# Cool_Stuff_USB_Hub.net
KiCad netlist of a schematic drawn in EasyEDA Pro
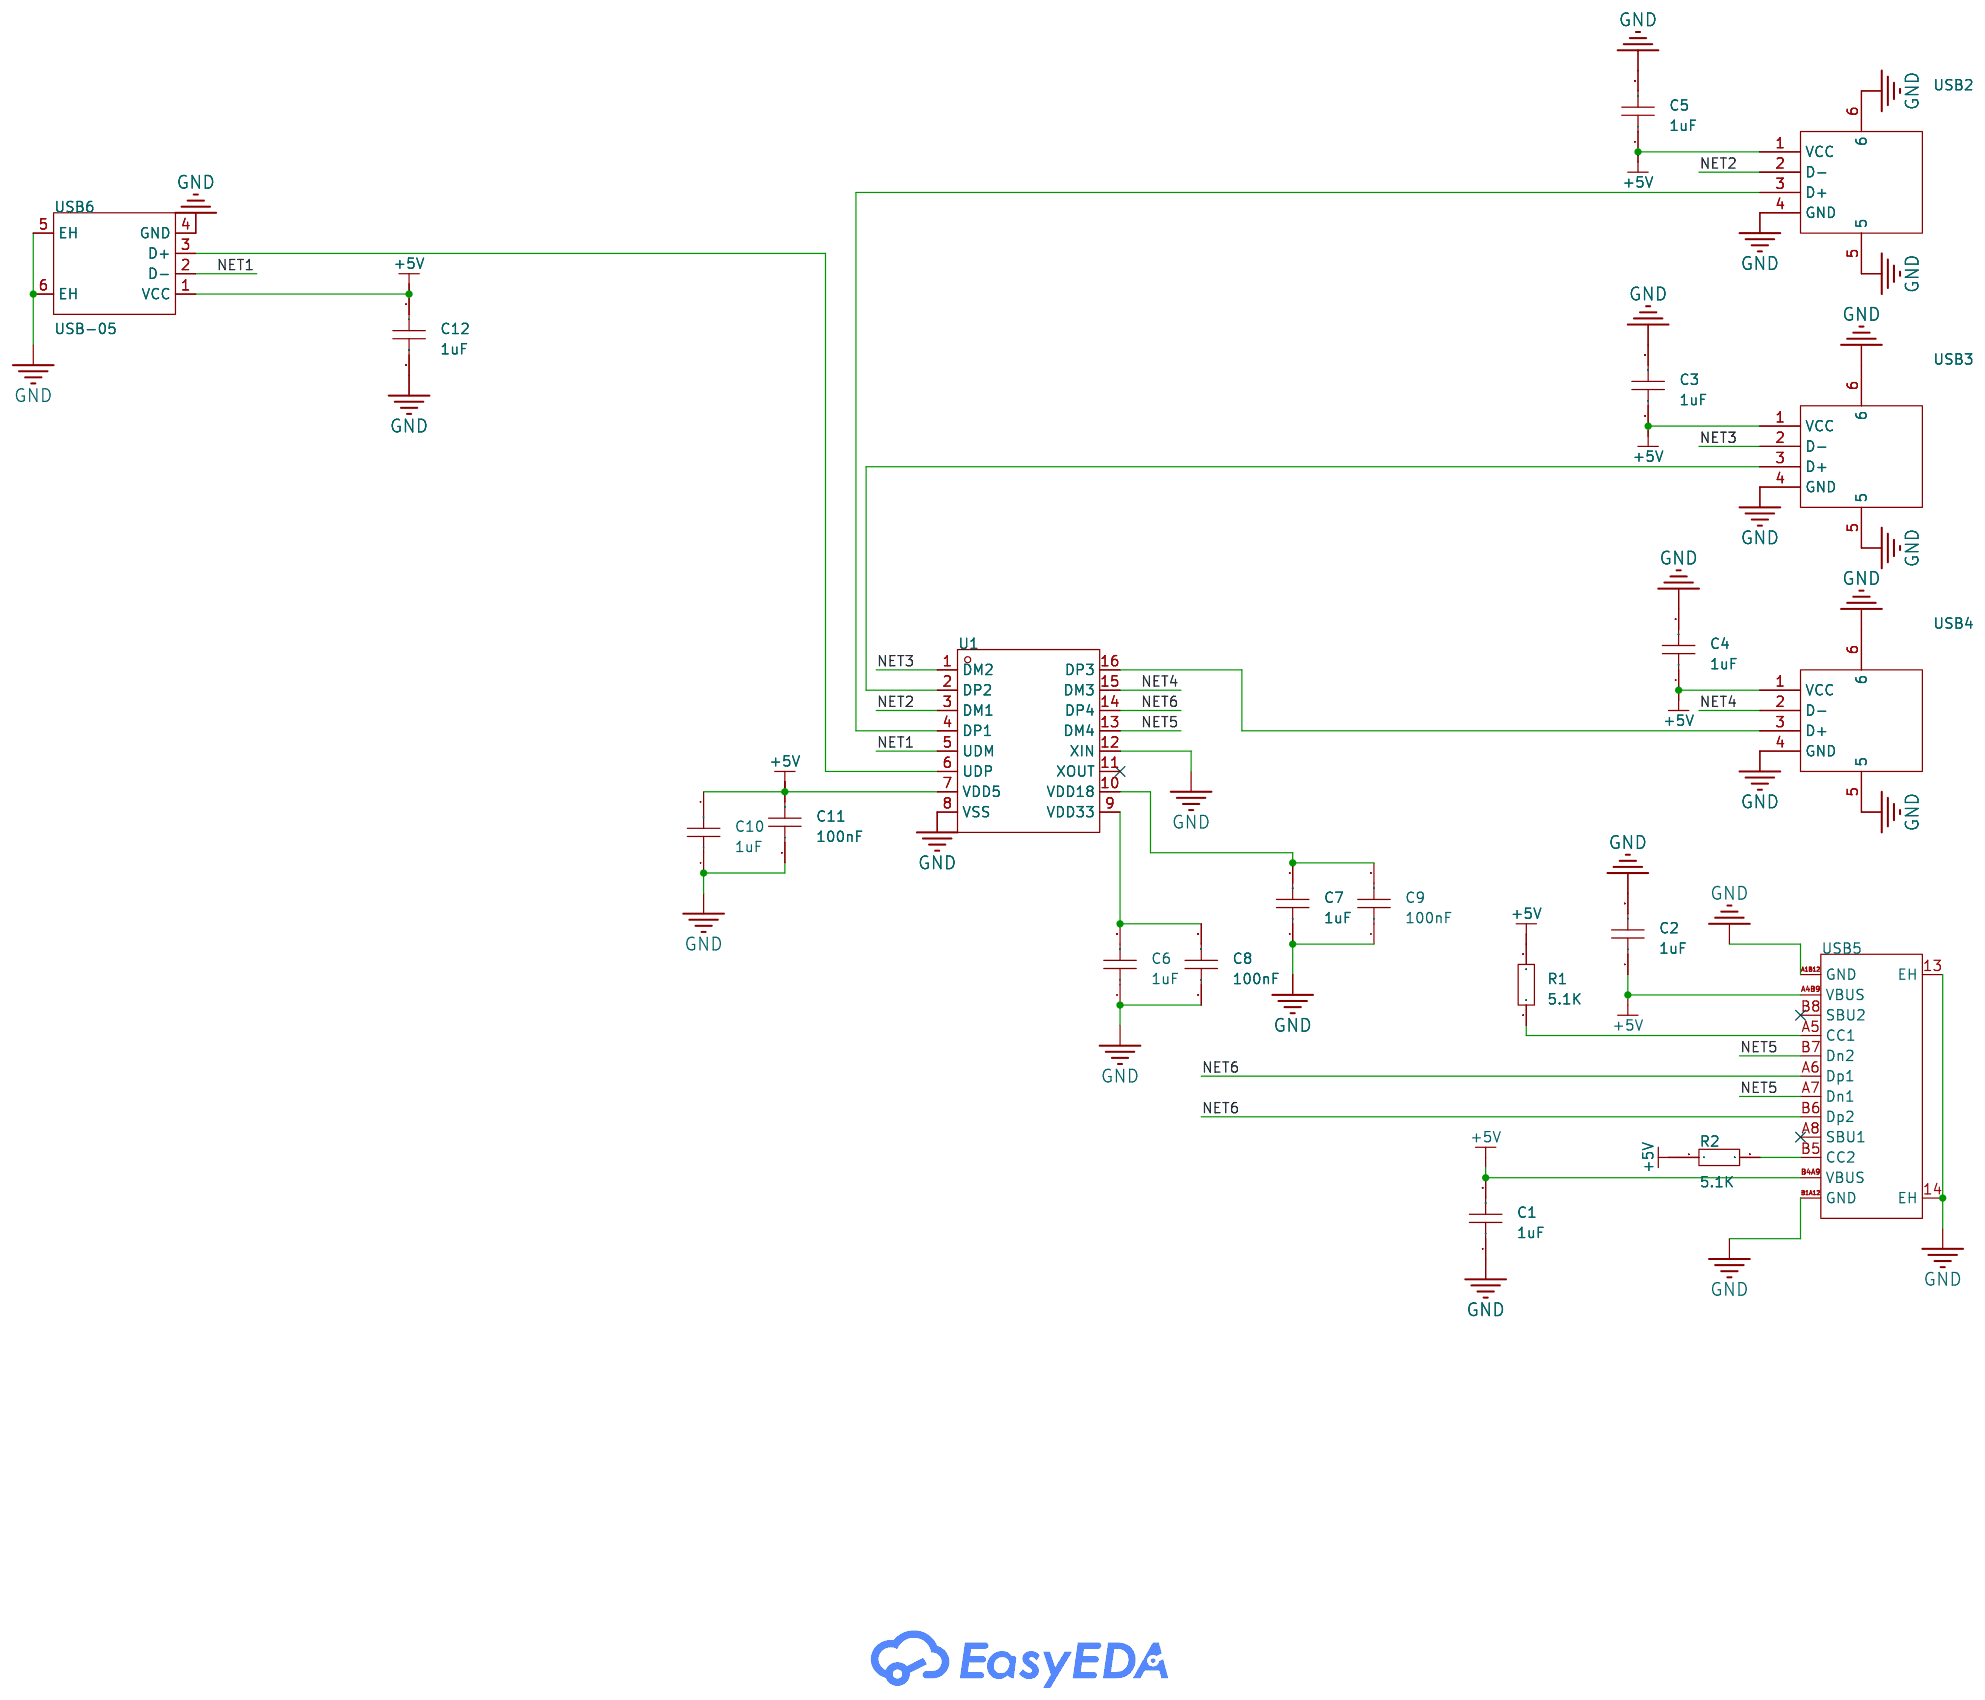
[diagram p0: schematic sheet]

(export (version "E")
  (design (tool "Eeschema 10.0.6"))
  (components
    (comp (ref "C1") (value "1uF") (footprint "easyedapro:C0603") (libsource (lib "easyedapro") (part "CAP")))
    (comp (ref "C2") (value "1uF") (footprint "easyedapro:C0603") (libsource (lib "easyedapro") (part "CAP")))
    (comp (ref "C3") (value "1uF") (footprint "easyedapro:C0603") (libsource (lib "easyedapro") (part "CAP")))
    (comp (ref "C4") (value "1uF") (footprint "easyedapro:C0603") (libsource (lib "easyedapro") (part "CAP")))
    (comp (ref "C5") (value "1uF") (footprint "easyedapro:C0603") (libsource (lib "easyedapro") (part "CAP")))
    (comp (ref "C6") (value "1uF") (footprint "easyedapro:C0603") (libsource (lib "easyedapro") (part "CAP")))
    (comp (ref "C7") (value "1uF") (footprint "easyedapro:C0603") (libsource (lib "easyedapro") (part "CAP")))
    (comp (ref "C8")
      (value "100nF")
      (footprint "easyedapro:C0603")
      (libsource (lib "easyedapro") (part "CAP"))
    )
    (comp (ref "C9")
      (value "100nF")
      (footprint "easyedapro:C0603")
      (libsource (lib "easyedapro") (part "CAP"))
    )
    (comp (ref "C10")
      (value "1uF")
      (footprint "easyedapro:C0603")
      (libsource (lib "easyedapro") (part "CAP"))
    )
    (comp (ref "C11")
      (value "100nF")
      (footprint "easyedapro:C0603")
      (libsource (lib "easyedapro") (part "CAP"))
    )
    (comp (ref "C12")
      (value "1uF")
      (footprint "easyedapro:C0603")
      (libsource (lib "easyedapro") (part "CAP"))
    )
    (comp (ref "R1")
      (value "5.1K")
      (footprint "easyedapro:R0603")
      (libsource (lib "easyedapro") (part "Res"))
    )
    (comp (ref "R2")
      (value "5.1K")
      (footprint "easyedapro:R0603")
      (libsource (lib "easyedapro") (part "Res"))
    )
    (comp (ref "U1")
      (value "SL2.1s")
      (footprint "easyedapro:SSOP-16_L4.6-W2.6-P0.53-LS4.0-BL")
      (fields (field (name "Manufacturer") "CoreChips(和芯润德)"))
      (libsource (lib "easyedapro") (part "SL2.1S"))
    )
    (comp (ref "USB2")
      (value "10.0 QHHTZB6.3")
      (footprint "easyedapro:USB-A-TH_10.0QHHTZB6.3")
      (fields (field (name "Manufacturer") "SHOU HAN(首韩)"))
      (libsource (lib "easyedapro") (part "10.0 QHHTZB6.3"))
    )
    (comp (ref "USB3")
      (value "10.0 QHHTZB6.3")
      (footprint "easyedapro:USB-A-TH_10.0QHHTZB6.3")
      (fields (field (name "Manufacturer") "SHOU HAN(首韩)"))
      (libsource (lib "easyedapro") (part "10.0 QHHTZB6.3"))
    )
    (comp (ref "USB4")
      (value "10.0 QHHTZB6.3")
      (footprint "easyedapro:USB-A-TH_10.0QHHTZB6.3")
      (fields (field (name "Manufacturer") "SHOU HAN(首韩)"))
      (libsource (lib "easyedapro") (part "10.0 QHHTZB6.3"))
    )
    (comp (ref "USB5")
      (value "TYPE-C 16PIN 2MD(073)")
      (footprint "easyedapro:USB-C-SMD_TYPE-C-16PIN-2MD-073")
      (fields (field (name "Manufacturer") "SHOU HAN(首韩)"))
      (libsource (lib "easyedapro") (part "TYPE-C 16PIN 2MD(073)"))
    )
    (comp (ref "USB6")
      (value "USB-05")
      (footprint "easyedapro:USB-A-TH_USB-05")
      (fields (field (name "Manufacturer") "SOFNG(硕方)"))
      (libsource (lib "easyedapro") (part "USB-05"))
    )
  )
  (nets
    (net (code "1") (name "+5V") (class "Default")
      (node (ref "C1") (pin "2") (pinfunction "2_2") (pintype "input"))
      (node (ref "C10") (pin "2") (pinfunction "2_2") (pintype "input"))
      (node (ref "C11") (pin "2") (pinfunction "2_2") (pintype "input"))
      (node (ref "C12") (pin "1") (pinfunction "1_1") (pintype "input"))
      (node (ref "C2") (pin "1") (pinfunction "1_1") (pintype "input"))
      (node (ref "C3") (pin "1") (pinfunction "1_1") (pintype "input"))
      (node (ref "C4") (pin "1") (pinfunction "1_1") (pintype "input"))
      (node (ref "C5") (pin "1") (pinfunction "1_1") (pintype "input"))
      (node (ref "R1") (pin "2") (pinfunction "2_2") (pintype "input"))
      (node (ref "R2") (pin "1") (pinfunction "1_1") (pintype "input"))
      (node (ref "U1") (pin "7") (pinfunction "VDD5_7") (pintype "unspecified"))
      (node (ref "USB2") (pin "1") (pinfunction "VCC_1") (pintype "unspecified"))
      (node (ref "USB3") (pin "1") (pinfunction "VCC_1") (pintype "unspecified"))
      (node (ref "USB4") (pin "1") (pinfunction "VCC_1") (pintype "unspecified"))
      (node (ref "USB5") (pin "A4B9") (pinfunction "VBUS_A4B9") (pintype "unspecified"))
      (node (ref "USB5") (pin "B4A9") (pinfunction "VBUS_B4A9") (pintype "unspecified"))
      (node (ref "USB6") (pin "1") (pinfunction "VCC_1") (pintype "input"))
    )
    (net (code "2") (name "/NET1") (class "Default")
      (node (ref "U1") (pin "5") (pinfunction "UDM_5") (pintype "unspecified"))
      (node (ref "USB6") (pin "2") (pinfunction "D-_2") (pintype "input"))
    )
    (net (code "3") (name "/NET2") (class "Default")
      (node (ref "U1") (pin "3") (pinfunction "DM1_3") (pintype "unspecified"))
      (node (ref "USB2") (pin "2") (pinfunction "D-_2") (pintype "unspecified"))
    )
    (net (code "4") (name "/NET3") (class "Default")
      (node (ref "U1") (pin "1") (pinfunction "DM2_1") (pintype "unspecified"))
      (node (ref "USB3") (pin "2") (pinfunction "D-_2") (pintype "unspecified"))
    )
    (net (code "5") (name "/NET4") (class "Default")
      (node (ref "U1") (pin "15") (pinfunction "DM3_15") (pintype "unspecified"))
      (node (ref "USB4") (pin "2") (pinfunction "D-_2") (pintype "unspecified"))
    )
    (net (code "6") (name "/NET5") (class "Default")
      (node (ref "U1") (pin "13") (pinfunction "DM4_13") (pintype "unspecified"))
      (node (ref "USB5") (pin "A7") (pinfunction "Dn1_A7") (pintype "unspecified"))
      (node (ref "USB5") (pin "B7") (pinfunction "Dn2_B7") (pintype "unspecified"))
    )
    (net (code "7") (name "/NET6") (class "Default")
      (node (ref "U1") (pin "14") (pinfunction "DP4_14") (pintype "unspecified"))
      (node (ref "USB5") (pin "A6") (pinfunction "Dp1_A6") (pintype "unspecified"))
      (node (ref "USB5") (pin "B6") (pinfunction "Dp2_B6") (pintype "unspecified"))
    )
    (net (code "8") (name "GND") (class "Default")
      (node (ref "C1") (pin "1") (pinfunction "1_1") (pintype "input"))
      (node (ref "C10") (pin "1") (pinfunction "1_1") (pintype "input"))
      (node (ref "C11") (pin "1") (pinfunction "1_1") (pintype "input"))
      (node (ref "C12") (pin "2") (pinfunction "2_2") (pintype "input"))
      (node (ref "C2") (pin "2") (pinfunction "2_2") (pintype "input"))
      (node (ref "C3") (pin "2") (pinfunction "2_2") (pintype "input"))
      (node (ref "C4") (pin "2") (pinfunction "2_2") (pintype "input"))
      (node (ref "C5") (pin "2") (pinfunction "2_2") (pintype "input"))
      (node (ref "C6") (pin "1") (pinfunction "1_1") (pintype "input"))
      (node (ref "C7") (pin "1") (pinfunction "1_1") (pintype "input"))
      (node (ref "C8") (pin "1") (pinfunction "1_1") (pintype "input"))
      (node (ref "C9") (pin "1") (pinfunction "1_1") (pintype "input"))
      (node (ref "U1") (pin "12") (pinfunction "XIN_12") (pintype "unspecified"))
      (node (ref "U1") (pin "8") (pinfunction "VSS_8") (pintype "unspecified"))
      (node (ref "USB2") (pin "4") (pinfunction "GND_4") (pintype "unspecified"))
      (node (ref "USB2") (pin "5") (pinfunction "5_5") (pintype "unspecified"))
      (node (ref "USB2") (pin "6") (pinfunction "6_6") (pintype "unspecified"))
      (node (ref "USB3") (pin "4") (pinfunction "GND_4") (pintype "unspecified"))
      (node (ref "USB3") (pin "5") (pinfunction "5_5") (pintype "unspecified"))
      (node (ref "USB3") (pin "6") (pinfunction "6_6") (pintype "unspecified"))
      (node (ref "USB4") (pin "4") (pinfunction "GND_4") (pintype "unspecified"))
      (node (ref "USB4") (pin "5") (pinfunction "5_5") (pintype "unspecified"))
      (node (ref "USB4") (pin "6") (pinfunction "6_6") (pintype "unspecified"))
      (node (ref "USB5") (pin "13") (pinfunction "EH_13") (pintype "unspecified"))
      (node (ref "USB5") (pin "14") (pinfunction "EH_14") (pintype "unspecified"))
      (node (ref "USB5") (pin "A1B12") (pinfunction "GND_A1B12") (pintype "unspecified"))
      (node (ref "USB5") (pin "B1A12") (pinfunction "GND_B1A12") (pintype "unspecified"))
      (node (ref "USB6") (pin "4") (pinfunction "GND_4") (pintype "input"))
      (node (ref "USB6") (pin "5") (pinfunction "EH_5") (pintype "unspecified"))
      (node (ref "USB6") (pin "6") (pinfunction "EH_6") (pintype "unspecified"))
    )
    (net (code "9") (name "Net-(U1-DP1)") (class "Default")
      (node (ref "U1") (pin "4") (pinfunction "DP1_4") (pintype "unspecified"))
      (node (ref "USB2") (pin "3") (pinfunction "D+_3") (pintype "unspecified"))
    )
    (net (code "10") (name "Net-(U1-DP2)") (class "Default")
      (node (ref "U1") (pin "2") (pinfunction "DP2_2") (pintype "unspecified"))
      (node (ref "USB3") (pin "3") (pinfunction "D+_3") (pintype "unspecified"))
    )
    (net (code "11") (name "Net-(U1-DP3)") (class "Default")
      (node (ref "U1") (pin "16") (pinfunction "DP3_16") (pintype "unspecified"))
      (node (ref "USB4") (pin "3") (pinfunction "D+_3") (pintype "unspecified"))
    )
    (net (code "12") (name "Net-(U1-UDP)") (class "Default")
      (node (ref "U1") (pin "6") (pinfunction "UDP_6") (pintype "unspecified"))
      (node (ref "USB6") (pin "3") (pinfunction "D+_3") (pintype "input"))
    )
    (net (code "13") (name "Net-(U1-VDD18)") (class "Default")
      (node (ref "C7") (pin "2") (pinfunction "2_2") (pintype "input"))
      (node (ref "C9") (pin "2") (pinfunction "2_2") (pintype "input"))
      (node (ref "U1") (pin "10") (pinfunction "VDD18_10") (pintype "unspecified"))
    )
    (net (code "14") (name "Net-(U1-VDD33)") (class "Default")
      (node (ref "C6") (pin "2") (pinfunction "2_2") (pintype "input"))
      (node (ref "C8") (pin "2") (pinfunction "2_2") (pintype "input"))
      (node (ref "U1") (pin "9") (pinfunction "VDD33_9") (pintype "unspecified"))
    )
    (net (code "15") (name "Net-(USB5-CC1)") (class "Default")
      (node (ref "R1") (pin "1") (pinfunction "1_1") (pintype "input"))
      (node (ref "USB5") (pin "A5") (pinfunction "CC1_A5") (pintype "unspecified"))
    )
    (net (code "16") (name "Net-(USB5-CC2)") (class "Default")
      (node (ref "R2") (pin "2") (pinfunction "2_2") (pintype "input"))
      (node (ref "USB5") (pin "B5") (pinfunction "CC2_B5") (pintype "unspecified"))
    )
    (net (code "17") (name "unconnected-(U1-XOUT-Pad11)") (class "Default")
      (node (ref "U1") (pin "11") (pinfunction "XOUT_11") (pintype "unspecified+no_connect"))
    )
    (net (code "18") (name "unconnected-(USB5-SBU1-PadA8)") (class "Default")
      (node (ref "USB5") (pin "A8") (pinfunction "SBU1_A8") (pintype "unspecified+no_connect"))
    )
    (net (code "19") (name "unconnected-(USB5-SBU2-PadB8)") (class "Default")
      (node (ref "USB5") (pin "B8") (pinfunction "SBU2_B8") (pintype "unspecified+no_connect"))
    )
  )
)
